# Control_Processing_Unit.net
KiCad netlist of a schematic drawn in Altium Designer
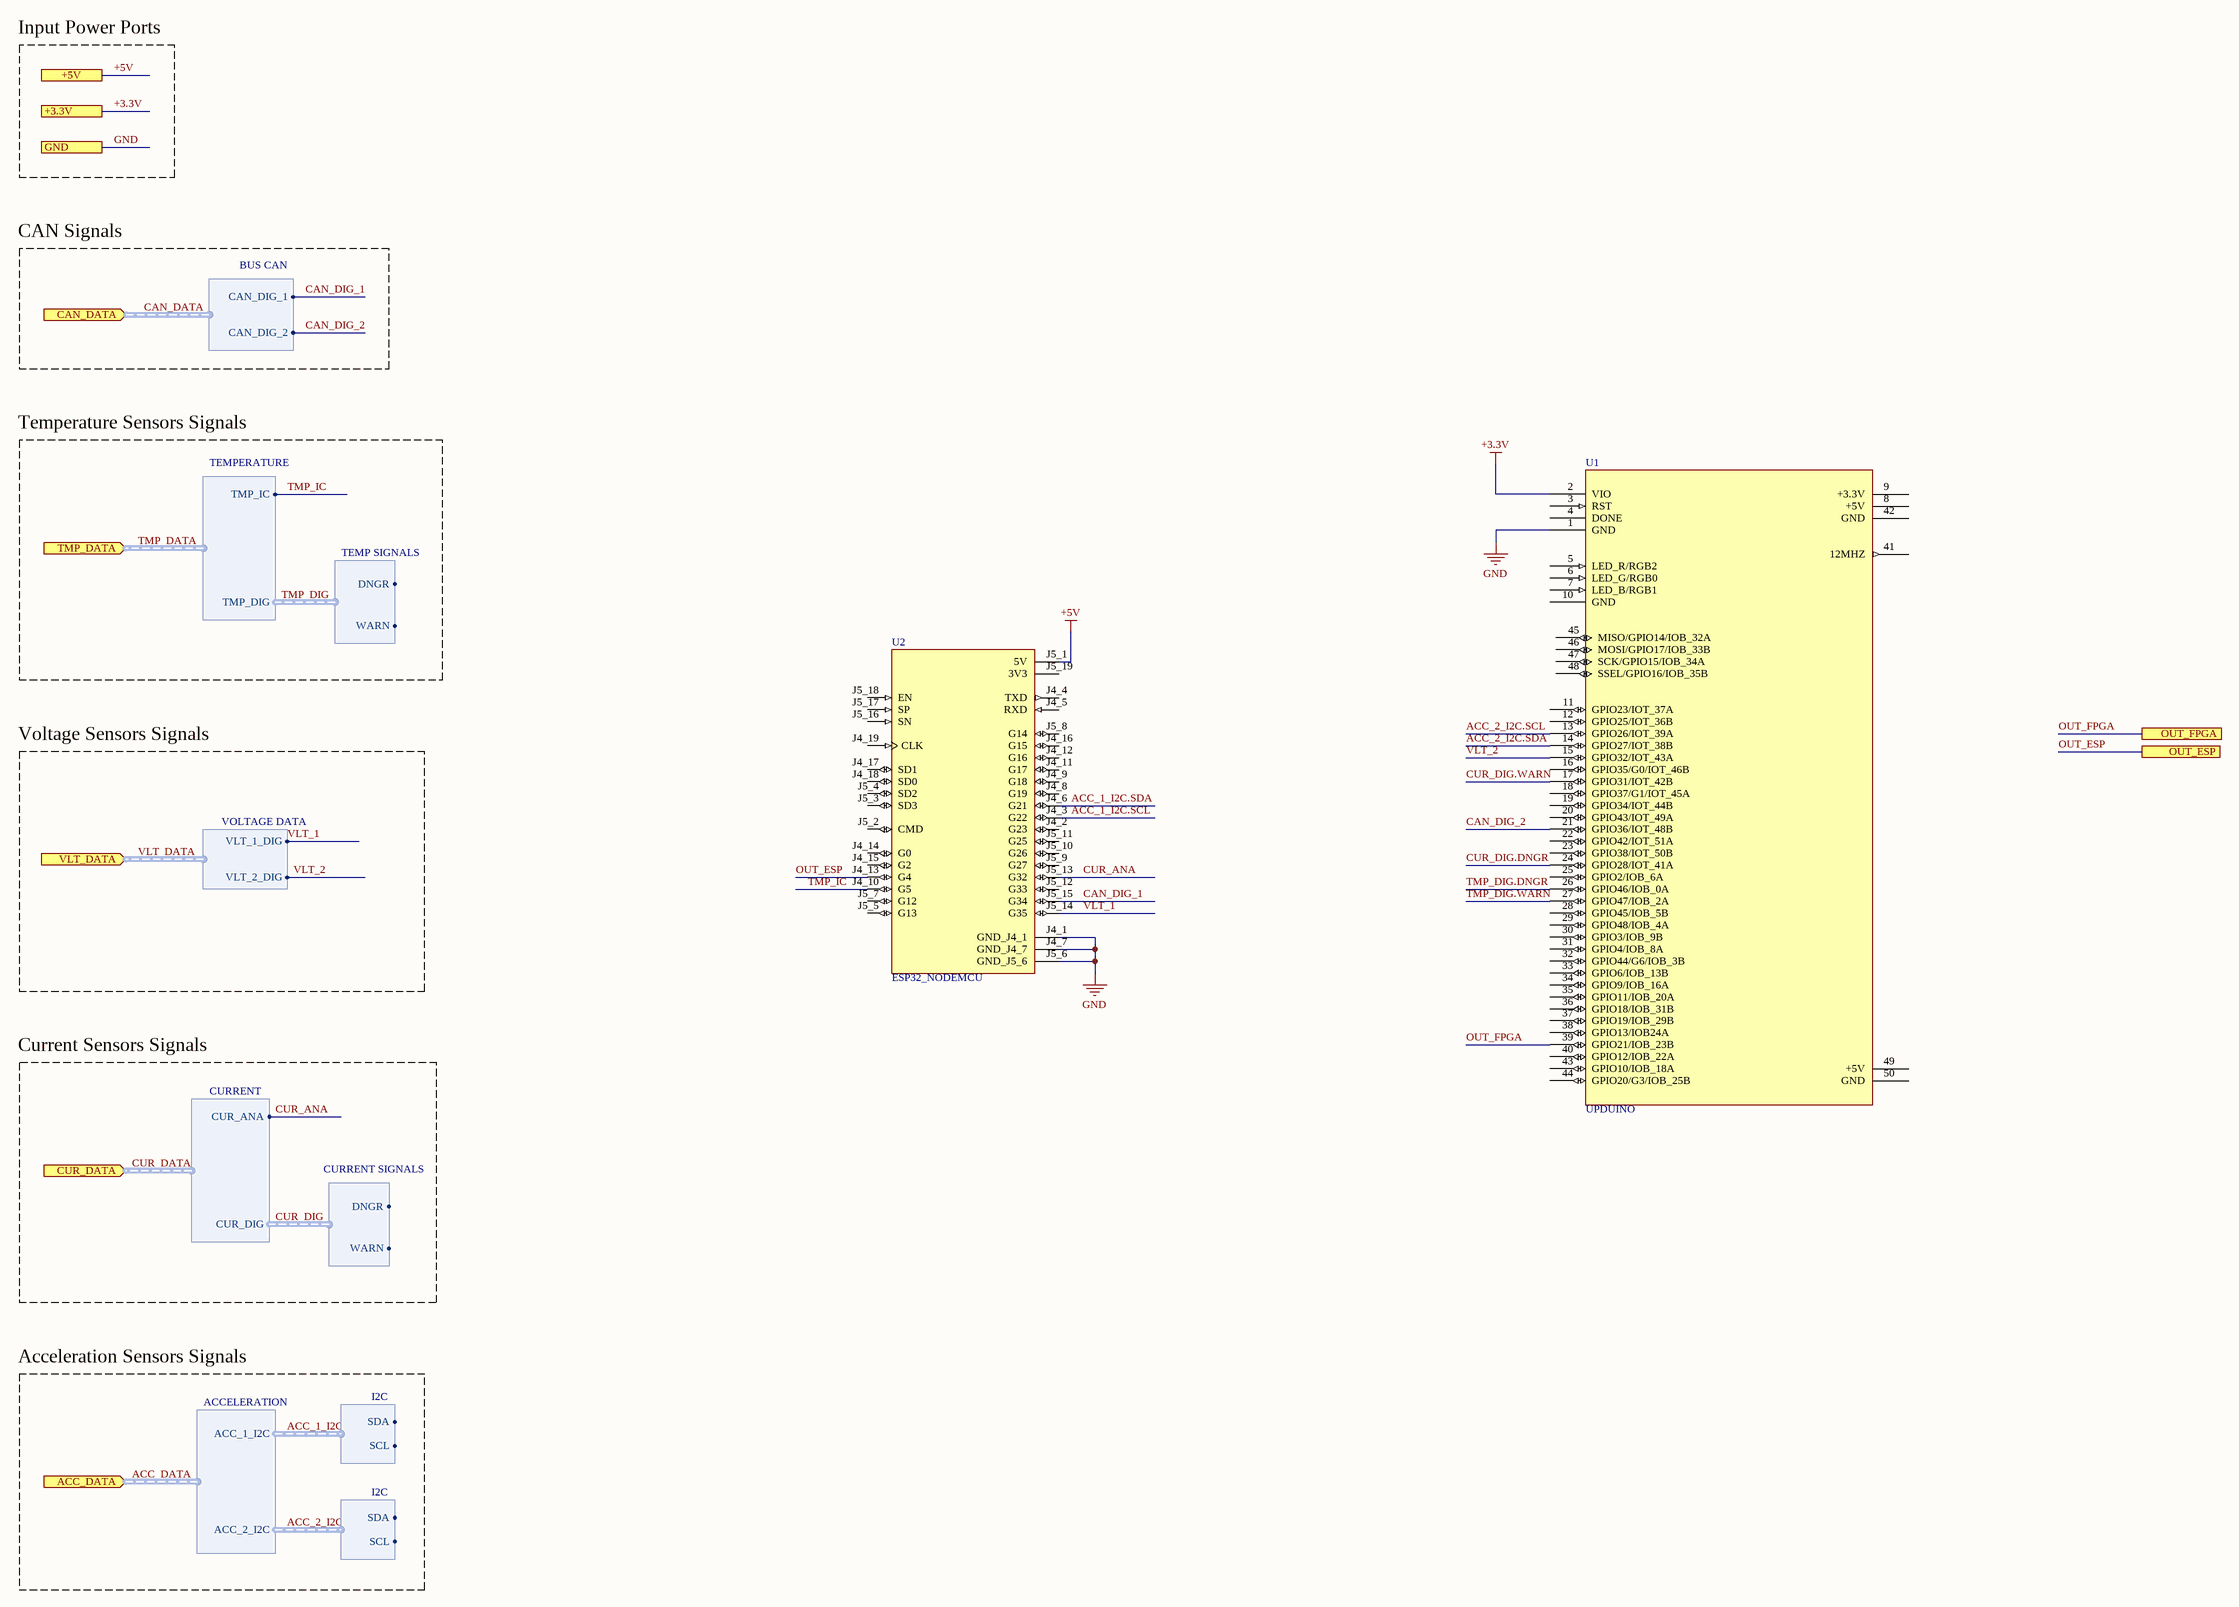
[diagram p0: Control_Processing_Unit.SchDoc]

(export (version "E")
  (design (tool "Eeschema 10.0.6"))
  (components
    (comp (ref "U1")
      (value "UPDUINO")
      (footprint "UPDUINO")
      (description "Lattice UltraPlus ICE40UP5K FPGA with 5.3K LUTs, 1Mb SPRAM, 120Kb DPRAM, 8 Multipliers")
      (libsource (lib "SiProFaSi") (part "UPDUINO"))
    )
    (comp (ref "U2")
      (value "ESP32_NODEMCU")
      (footprint "MODULE_ESP32_NODEMCU")
      (fields (field (name "MF") "Espressif Systems") (field (name "MP") "ESP32 NODEMCU"))
      (libsource (lib "TD") (part "ESP32_NODEMCU"))
    )
  )
  (nets
    (net (code "14") (name "+3.3V") (class "Default")
      (node (ref "U1") (pin "2") (pinfunction "VIO_2") (pintype "power_in"))
    )
    (net (code "15") (name "+5V") (class "Default")
      (node (ref "U2") (pin "J5_1") (pinfunction "5V_J5_1") (pintype "power_in"))
    )
    (net (code "16") (name "/ACC_1_I2C.SCL") (class "Default")
      (node (ref "U2") (pin "J4_3") (pinfunction "G22_J4_3") (pintype "bidirectional"))
    )
    (net (code "17") (name "/ACC_1_I2C.SDA") (class "Default")
      (node (ref "U2") (pin "J4_6") (pinfunction "G21_J4_6") (pintype "bidirectional"))
    )
    (net (code "19") (name "/ACC_2_I2C.SCL") (class "Default")
      (node (ref "U1") (pin "13") (pinfunction "GPIO26/IOT_39A_13") (pintype "bidirectional"))
    )
    (net (code "20") (name "/ACC_2_I2C.SDA") (class "Default")
      (node (ref "U1") (pin "14") (pinfunction "GPIO27/IOT_38B_14") (pintype "bidirectional"))
    )
    (net (code "23") (name "/CAN_DIG_1") (class "Default")
      (node (ref "U2") (pin "J5_15") (pinfunction "G34_J5_15") (pintype "bidirectional"))
    )
    (net (code "24") (name "/CAN_DIG_2") (class "Default")
      (node (ref "U1") (pin "21") (pinfunction "GPIO36/IOT_48B_21") (pintype "bidirectional"))
    )
    (net (code "25") (name "/CUR_ANA") (class "Default")
      (node (ref "U2") (pin "J5_13") (pinfunction "G32_J5_13") (pintype "bidirectional"))
    )
    (net (code "26") (name "/CUR_DIG.DNGR") (class "Default")
      (node (ref "U1") (pin "24") (pinfunction "GPIO28/IOT_41A_24") (pintype "bidirectional"))
    )
    (net (code "27") (name "/CUR_DIG.WARN") (class "Default")
      (node (ref "U1") (pin "17") (pinfunction "GPIO31/IOT_42B_17") (pintype "bidirectional"))
    )
    (net (code "29") (name "/OUT_ESP") (class "Default")
      (node (ref "U2") (pin "J4_13") (pinfunction "G4_J4_13") (pintype "bidirectional"))
    )
    (net (code "30") (name "/OUT_FPGA") (class "Default")
      (node (ref "U1") (pin "39") (pinfunction "GPIO21/IOB_23B_39") (pintype "bidirectional"))
    )
    (net (code "31") (name "/TMP_DIG.DNGR") (class "Default")
      (node (ref "U1") (pin "26") (pinfunction "GPIO46/IOB_0A_26") (pintype "bidirectional"))
    )
    (net (code "32") (name "/TMP_DIG.WARN") (class "Default")
      (node (ref "U1") (pin "27") (pinfunction "GPIO47/IOB_2A_27") (pintype "bidirectional"))
    )
    (net (code "34") (name "/TMP_IC") (class "Default")
      (node (ref "U2") (pin "J4_10") (pinfunction "G5_J4_10") (pintype "bidirectional"))
    )
    (net (code "35") (name "/VLT_1") (class "Default")
      (node (ref "U2") (pin "J5_14") (pinfunction "G35_J5_14") (pintype "bidirectional"))
    )
    (net (code "36") (name "/VLT_2") (class "Default")
      (node (ref "U1") (pin "15") (pinfunction "GPIO32/IOT_43A_15") (pintype "bidirectional"))
    )
    (net (code "41") (name "GND") (class "Default")
      (node (ref "U1") (pin "1") (pinfunction "GND_1") (pintype "passive"))
      (node (ref "U2") (pin "J4_1") (pinfunction "GND_J4_1_J4_1") (pintype "power_in"))
      (node (ref "U2") (pin "J4_7") (pinfunction "GND_J4_7_J4_7") (pintype "power_in"))
      (node (ref "U2") (pin "J5_6") (pinfunction "GND_J5_6_J5_6") (pintype "power_in"))
    )
    (net (code "42") (name "unconnected-(U1-+3.3V-Pad9)") (class "Default")
      (node (ref "U1") (pin "9") (pinfunction "+3.3V_9") (pintype "power_in"))
    )
    (net (code "43") (name "unconnected-(U1-+5V-Pad8)") (class "Default")
      (node (ref "U1") (pin "8") (pinfunction "+5V_8") (pintype "power_in"))
    )
    (net (code "44") (name "unconnected-(U1-+5V-Pad49)") (class "Default")
      (node (ref "U1") (pin "49") (pinfunction "+5V_49") (pintype "power_in"))
    )
    (net (code "45") (name "unconnected-(U1-12MHZ-Pad41)") (class "Default")
      (node (ref "U1") (pin "41") (pinfunction "12MHZ_41") (pintype "output"))
    )
    (net (code "46") (name "unconnected-(U1-DONE-Pad4)") (class "Default")
      (node (ref "U1") (pin "4") (pinfunction "DONE_4") (pintype "passive"))
    )
    (net (code "47") (name "unconnected-(U1-GND-Pad10)") (class "Default")
      (node (ref "U1") (pin "10") (pinfunction "GND_10") (pintype "passive"))
    )
    (net (code "48") (name "unconnected-(U1-GND-Pad42)") (class "Default")
      (node (ref "U1") (pin "42") (pinfunction "GND_42") (pintype "passive"))
    )
    (net (code "49") (name "unconnected-(U1-GND-Pad50)") (class "Default")
      (node (ref "U1") (pin "50") (pinfunction "GND_50") (pintype "passive"))
    )
    (net (code "50") (name "unconnected-(U1-GPIO2{slash}IOB_6A-Pad25)") (class "Default")
      (node (ref "U1") (pin "25") (pinfunction "GPIO2/IOB_6A_25") (pintype "bidirectional"))
    )
    (net (code "51") (name "unconnected-(U1-GPIO3{slash}IOB_9B-Pad30)") (class "Default")
      (node (ref "U1") (pin "30") (pinfunction "GPIO3/IOB_9B_30") (pintype "bidirectional"))
    )
    (net (code "52") (name "unconnected-(U1-GPIO4{slash}IOB_8A-Pad31)") (class "Default")
      (node (ref "U1") (pin "31") (pinfunction "GPIO4/IOB_8A_31") (pintype "bidirectional"))
    )
    (net (code "53") (name "unconnected-(U1-GPIO6{slash}IOB_13B-Pad33)") (class "Default")
      (node (ref "U1") (pin "33") (pinfunction "GPIO6/IOB_13B_33") (pintype "bidirectional"))
    )
    (net (code "54") (name "unconnected-(U1-GPIO9{slash}IOB_16A-Pad34)") (class "Default")
      (node (ref "U1") (pin "34") (pinfunction "GPIO9/IOB_16A_34") (pintype "bidirectional"))
    )
    (net (code "55") (name "unconnected-(U1-GPIO10{slash}IOB_18A-Pad43)") (class "Default")
      (node (ref "U1") (pin "43") (pinfunction "GPIO10/IOB_18A_43") (pintype "bidirectional"))
    )
    (net (code "56") (name "unconnected-(U1-GPIO11{slash}IOB_20A-Pad35)") (class "Default")
      (node (ref "U1") (pin "35") (pinfunction "GPIO11/IOB_20A_35") (pintype "bidirectional"))
    )
    (net (code "57") (name "unconnected-(U1-GPIO12{slash}IOB_22A-Pad40)") (class "Default")
      (node (ref "U1") (pin "40") (pinfunction "GPIO12/IOB_22A_40") (pintype "bidirectional"))
    )
    (net (code "58") (name "unconnected-(U1-GPIO13{slash}IOB24A-Pad38)") (class "Default")
      (node (ref "U1") (pin "38") (pinfunction "GPIO13/IOB24A_38") (pintype "bidirectional"))
    )
    (net (code "59") (name "unconnected-(U1-GPIO18{slash}IOB_31B-Pad36)") (class "Default")
      (node (ref "U1") (pin "36") (pinfunction "GPIO18/IOB_31B_36") (pintype "bidirectional"))
    )
    (net (code "60") (name "unconnected-(U1-GPIO19{slash}IOB_29B-Pad37)") (class "Default")
      (node (ref "U1") (pin "37") (pinfunction "GPIO19/IOB_29B_37") (pintype "bidirectional"))
    )
    (net (code "61") (name "unconnected-(U1-GPIO20{slash}G3{slash}IOB_25B-Pad44)") (class "Default")
      (node (ref "U1") (pin "44") (pinfunction "GPIO20/G3/IOB_25B_44") (pintype "bidirectional"))
    )
    (net (code "62") (name "unconnected-(U1-GPIO23{slash}IOT_37A-Pad11)") (class "Default")
      (node (ref "U1") (pin "11") (pinfunction "GPIO23/IOT_37A_11") (pintype "bidirectional"))
    )
    (net (code "63") (name "unconnected-(U1-GPIO25{slash}IOT_36B-Pad12)") (class "Default")
      (node (ref "U1") (pin "12") (pinfunction "GPIO25/IOT_36B_12") (pintype "bidirectional"))
    )
    (net (code "64") (name "unconnected-(U1-GPIO34{slash}IOT_44B-Pad19)") (class "Default")
      (node (ref "U1") (pin "19") (pinfunction "GPIO34/IOT_44B_19") (pintype "bidirectional"))
    )
    (net (code "65") (name "unconnected-(U1-GPIO35{slash}G0{slash}IOT_46B-Pad16)") (class "Default")
      (node (ref "U1") (pin "16") (pinfunction "GPIO35/G0/IOT_46B_16") (pintype "bidirectional"))
    )
    (net (code "66") (name "unconnected-(U1-GPIO37{slash}G1{slash}IOT_45A-Pad18)") (class "Default")
      (node (ref "U1") (pin "18") (pinfunction "GPIO37/G1/IOT_45A_18") (pintype "bidirectional"))
    )
    (net (code "67") (name "unconnected-(U1-GPIO38{slash}IOT_50B-Pad23)") (class "Default")
      (node (ref "U1") (pin "23") (pinfunction "GPIO38/IOT_50B_23") (pintype "bidirectional"))
    )
    (net (code "68") (name "unconnected-(U1-GPIO42{slash}IOT_51A-Pad22)") (class "Default")
      (node (ref "U1") (pin "22") (pinfunction "GPIO42/IOT_51A_22") (pintype "bidirectional"))
    )
    (net (code "69") (name "unconnected-(U1-GPIO43{slash}IOT_49A-Pad20)") (class "Default")
      (node (ref "U1") (pin "20") (pinfunction "GPIO43/IOT_49A_20") (pintype "bidirectional"))
    )
    (net (code "70") (name "unconnected-(U1-GPIO44{slash}G6{slash}IOB_3B-Pad32)") (class "Default")
      (node (ref "U1") (pin "32") (pinfunction "GPIO44/G6/IOB_3B_32") (pintype "bidirectional"))
    )
    (net (code "71") (name "unconnected-(U1-GPIO45{slash}IOB_5B-Pad28)") (class "Default")
      (node (ref "U1") (pin "28") (pinfunction "GPIO45/IOB_5B_28") (pintype "bidirectional"))
    )
    (net (code "72") (name "unconnected-(U1-GPIO48{slash}IOB_4A-Pad29)") (class "Default")
      (node (ref "U1") (pin "29") (pinfunction "GPIO48/IOB_4A_29") (pintype "bidirectional"))
    )
    (net (code "73") (name "unconnected-(U1-LED_B{slash}RGB1-Pad7)") (class "Default")
      (node (ref "U1") (pin "7") (pinfunction "LED_B/RGB1_7") (pintype "input"))
    )
    (net (code "74") (name "unconnected-(U1-LED_G{slash}RGB0-Pad6)") (class "Default")
      (node (ref "U1") (pin "6") (pinfunction "LED_G/RGB0_6") (pintype "input"))
    )
    (net (code "75") (name "unconnected-(U1-LED_R{slash}RGB2-Pad5)") (class "Default")
      (node (ref "U1") (pin "5") (pinfunction "LED_R/RGB2_5") (pintype "input"))
    )
    (net (code "76") (name "unconnected-(U1-MISO{slash}GPIO14{slash}IOB_32A-Pad45)") (class "Default")
      (node (ref "U1") (pin "45") (pinfunction "MISO/GPIO14/IOB_32A_45") (pintype "bidirectional"))
    )
    (net (code "77") (name "unconnected-(U1-MOSI{slash}GPIO17{slash}IOB_33B-Pad46)") (class "Default")
      (node (ref "U1") (pin "46") (pinfunction "MOSI/GPIO17/IOB_33B_46") (pintype "bidirectional"))
    )
    (net (code "78") (name "unconnected-(U1-RST-Pad3)") (class "Default")
      (node (ref "U1") (pin "3") (pinfunction "RST_3") (pintype "input"))
    )
    (net (code "79") (name "unconnected-(U1-SCK{slash}GPIO15{slash}IOB_34A-Pad47)") (class "Default")
      (node (ref "U1") (pin "47") (pinfunction "SCK/GPIO15/IOB_34A_47") (pintype "bidirectional"))
    )
    (net (code "80") (name "unconnected-(U1-SSEL{slash}GPIO16{slash}IOB_35B-Pad48)") (class "Default")
      (node (ref "U1") (pin "48") (pinfunction "SSEL/GPIO16/IOB_35B_48") (pintype "bidirectional"))
    )
    (net (code "81") (name "unconnected-(U2-3V3-PadJ5_19)") (class "Default")
      (node (ref "U2") (pin "J5_19") (pinfunction "3V3_J5_19") (pintype "power_in"))
    )
    (net (code "82") (name "unconnected-(U2-CLK-PadJ4_19)") (class "Default")
      (node (ref "U2") (pin "J4_19") (pinfunction "CLK_J4_19") (pintype "input"))
    )
    (net (code "83") (name "unconnected-(U2-CMD-PadJ5_2)") (class "Default")
      (node (ref "U2") (pin "J5_2") (pinfunction "CMD_J5_2") (pintype "bidirectional"))
    )
    (net (code "84") (name "unconnected-(U2-EN-PadJ5_18)") (class "Default")
      (node (ref "U2") (pin "J5_18") (pinfunction "EN_J5_18") (pintype "input"))
    )
    (net (code "85") (name "unconnected-(U2-G0-PadJ4_14)") (class "Default")
      (node (ref "U2") (pin "J4_14") (pinfunction "G0_J4_14") (pintype "bidirectional"))
    )
    (net (code "86") (name "unconnected-(U2-G2-PadJ4_15)") (class "Default")
      (node (ref "U2") (pin "J4_15") (pinfunction "G2_J4_15") (pintype "bidirectional"))
    )
    (net (code "87") (name "unconnected-(U2-G12-PadJ5_7)") (class "Default")
      (node (ref "U2") (pin "J5_7") (pinfunction "G12_J5_7") (pintype "bidirectional"))
    )
    (net (code "88") (name "unconnected-(U2-G13-PadJ5_5)") (class "Default")
      (node (ref "U2") (pin "J5_5") (pinfunction "G13_J5_5") (pintype "bidirectional"))
    )
    (net (code "89") (name "unconnected-(U2-G14-PadJ5_8)") (class "Default")
      (node (ref "U2") (pin "J5_8") (pinfunction "G14_J5_8") (pintype "bidirectional"))
    )
    (net (code "90") (name "unconnected-(U2-G15-PadJ4_16)") (class "Default")
      (node (ref "U2") (pin "J4_16") (pinfunction "G15_J4_16") (pintype "bidirectional"))
    )
    (net (code "91") (name "unconnected-(U2-G16-PadJ4_12)") (class "Default")
      (node (ref "U2") (pin "J4_12") (pinfunction "G16_J4_12") (pintype "bidirectional"))
    )
    (net (code "92") (name "unconnected-(U2-G17-PadJ4_11)") (class "Default")
      (node (ref "U2") (pin "J4_11") (pinfunction "G17_J4_11") (pintype "bidirectional"))
    )
    (net (code "93") (name "unconnected-(U2-G18-PadJ4_9)") (class "Default")
      (node (ref "U2") (pin "J4_9") (pinfunction "G18_J4_9") (pintype "bidirectional"))
    )
    (net (code "94") (name "unconnected-(U2-G19-PadJ4_8)") (class "Default")
      (node (ref "U2") (pin "J4_8") (pinfunction "G19_J4_8") (pintype "bidirectional"))
    )
    (net (code "95") (name "unconnected-(U2-G23-PadJ4_2)") (class "Default")
      (node (ref "U2") (pin "J4_2") (pinfunction "G23_J4_2") (pintype "bidirectional"))
    )
    (net (code "96") (name "unconnected-(U2-G25-PadJ5_11)") (class "Default")
      (node (ref "U2") (pin "J5_11") (pinfunction "G25_J5_11") (pintype "bidirectional"))
    )
    (net (code "97") (name "unconnected-(U2-G26-PadJ5_10)") (class "Default")
      (node (ref "U2") (pin "J5_10") (pinfunction "G26_J5_10") (pintype "bidirectional"))
    )
    (net (code "98") (name "unconnected-(U2-G27-PadJ5_9)") (class "Default")
      (node (ref "U2") (pin "J5_9") (pinfunction "G27_J5_9") (pintype "bidirectional"))
    )
    (net (code "99") (name "unconnected-(U2-G33-PadJ5_12)") (class "Default")
      (node (ref "U2") (pin "J5_12") (pinfunction "G33_J5_12") (pintype "bidirectional"))
    )
    (net (code "100") (name "unconnected-(U2-RXD-PadJ4_5)") (class "Default")
      (node (ref "U2") (pin "J4_5") (pinfunction "RXD_J4_5") (pintype "input"))
    )
    (net (code "101") (name "unconnected-(U2-SD0-PadJ4_18)") (class "Default")
      (node (ref "U2") (pin "J4_18") (pinfunction "SD0_J4_18") (pintype "bidirectional"))
    )
    (net (code "102") (name "unconnected-(U2-SD1-PadJ4_17)") (class "Default")
      (node (ref "U2") (pin "J4_17") (pinfunction "SD1_J4_17") (pintype "bidirectional"))
    )
    (net (code "103") (name "unconnected-(U2-SD2-PadJ5_4)") (class "Default")
      (node (ref "U2") (pin "J5_4") (pinfunction "SD2_J5_4") (pintype "bidirectional"))
    )
    (net (code "104") (name "unconnected-(U2-SD3-PadJ5_3)") (class "Default")
      (node (ref "U2") (pin "J5_3") (pinfunction "SD3_J5_3") (pintype "bidirectional"))
    )
    (net (code "105") (name "unconnected-(U2-SN-PadJ5_16)") (class "Default")
      (node (ref "U2") (pin "J5_16") (pinfunction "SN_J5_16") (pintype "input"))
    )
    (net (code "106") (name "unconnected-(U2-SP-PadJ5_17)") (class "Default")
      (node (ref "U2") (pin "J5_17") (pinfunction "SP_J5_17") (pintype "input"))
    )
    (net (code "107") (name "unconnected-(U2-TXD-PadJ4_4)") (class "Default")
      (node (ref "U2") (pin "J4_4") (pinfunction "TXD_J4_4") (pintype "output"))
    )
  )
)
